# Sheet1.net
KiCad netlist of a schematic drawn in Altium Designer
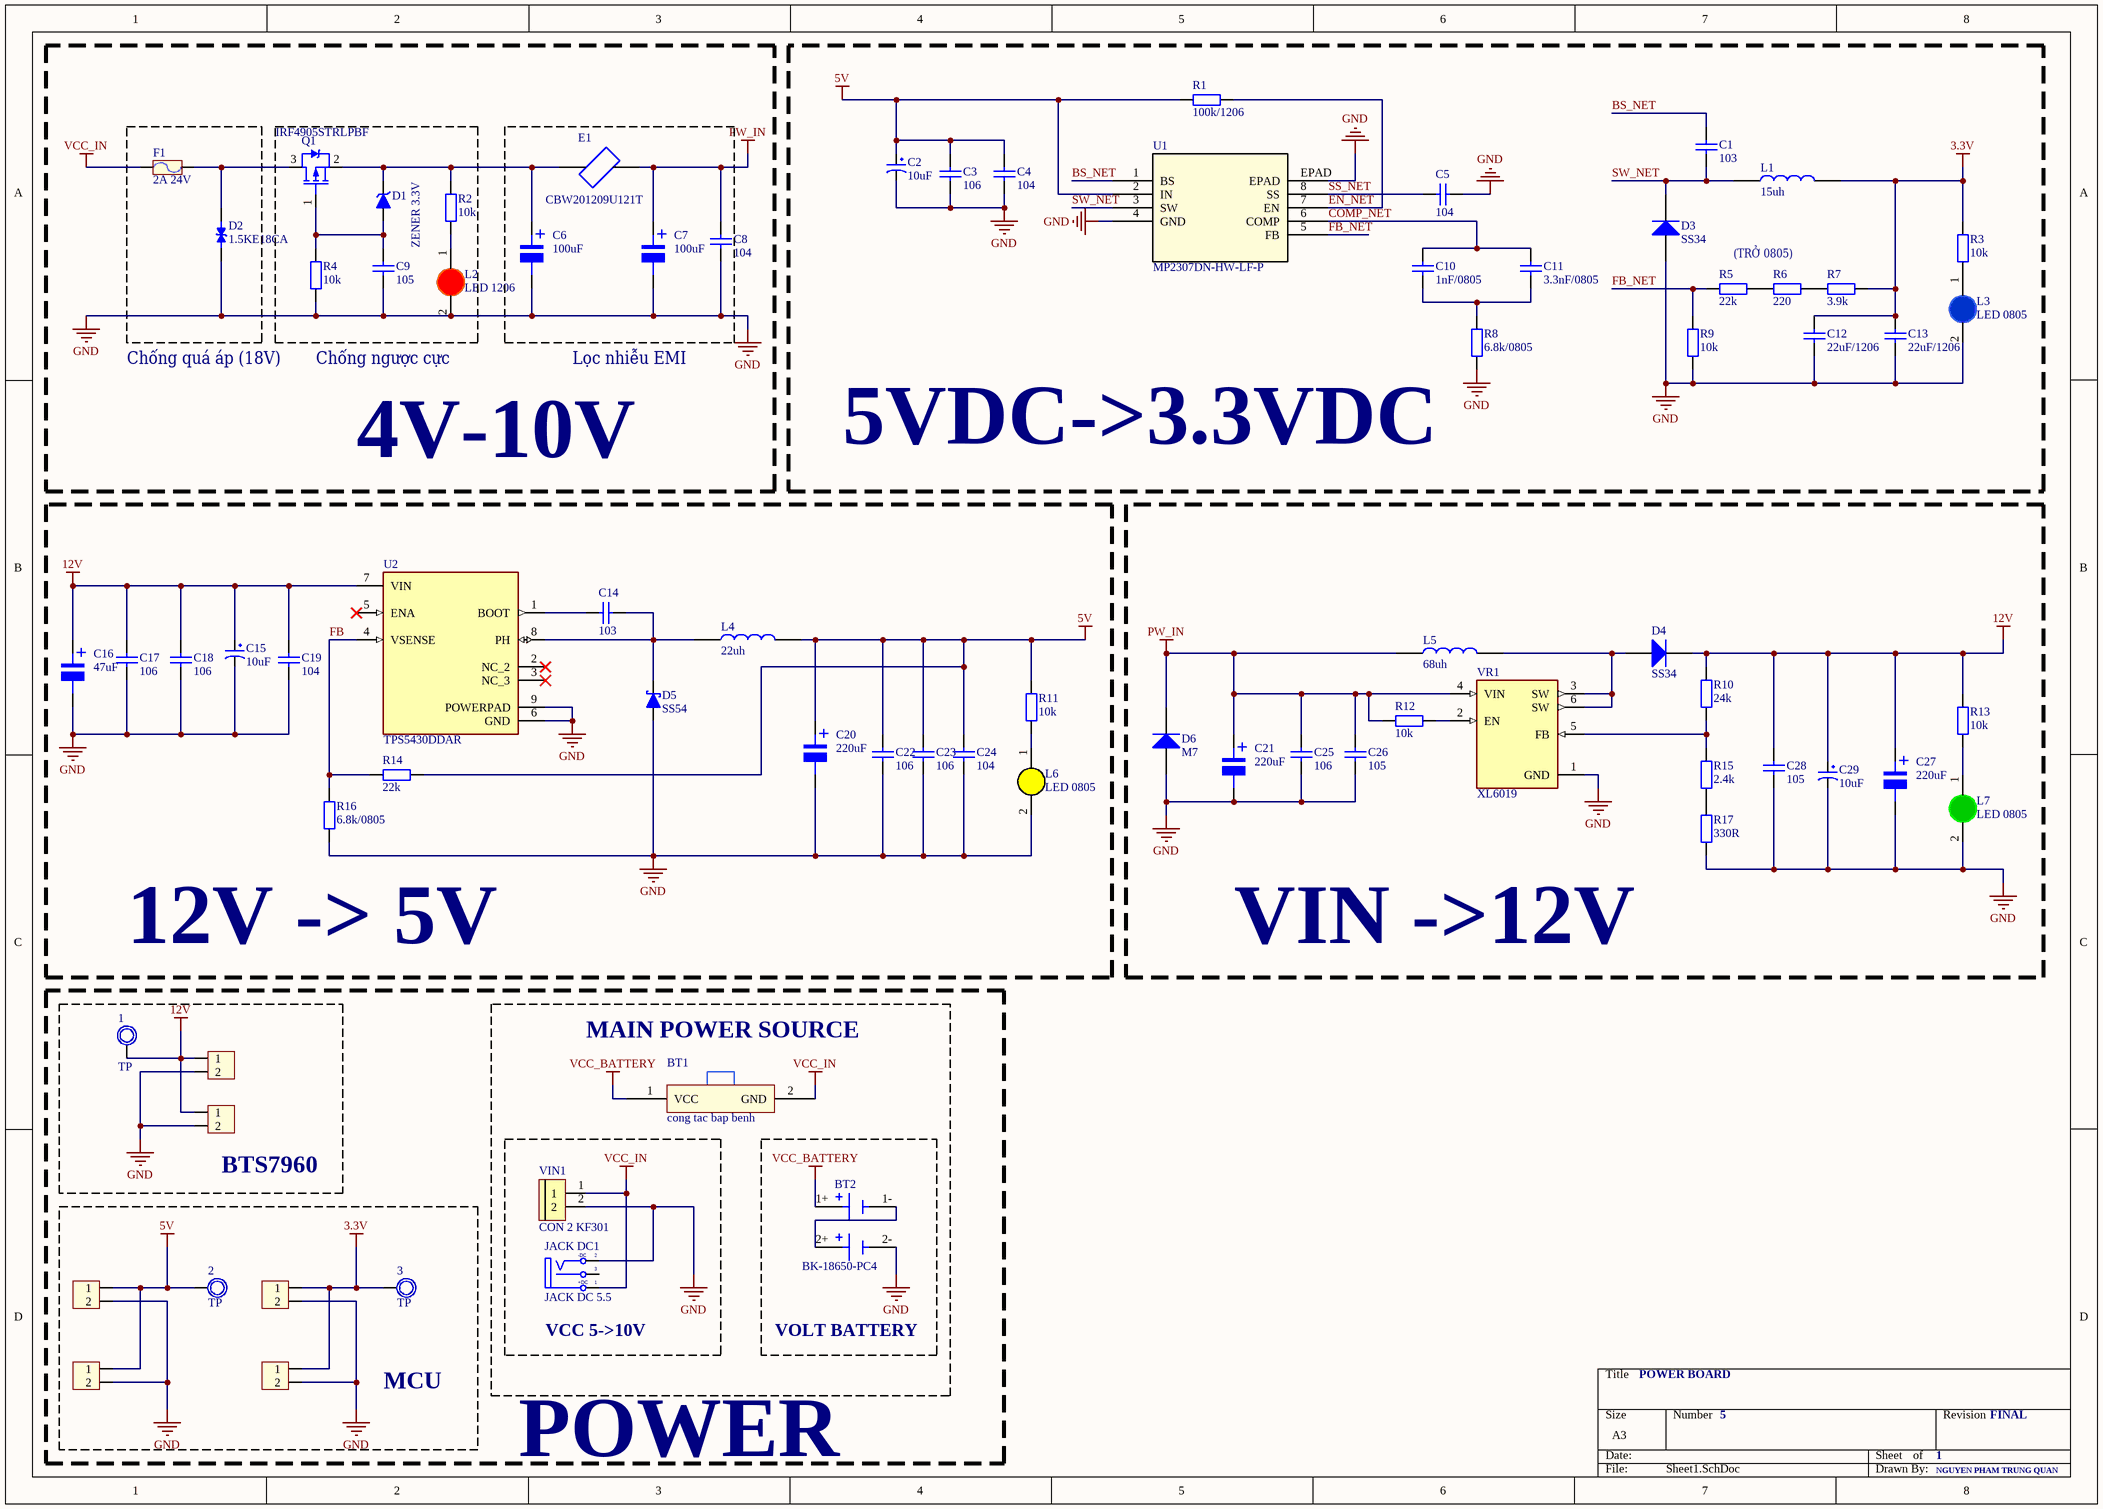
[diagram p0: Sheet1.SchDoc]

(export (version "E")
  (design (tool "Eeschema 10.0.6"))
  (components
    (comp (ref "1")
      (value "TP")
      (footprint "TP1")
      (description "Test Point")
      (libsource (lib "") (part "TP1_1"))
    )
    (comp (ref "2")
      (value "TP")
      (footprint "TP1")
      (description "Test Point")
      (libsource (lib "syhaunguyen") (part "TP1"))
    )
    (comp (ref "3")
      (value "TP")
      (footprint "TP1")
      (description "Test Point")
      (libsource (lib "syhaunguyen") (part "TP1"))
    )
    (comp (ref "BT1")
      (value "cong tac bap benh")
      (footprint "CONG TAC BAP BENH")
      (libsource (lib "Integrated_Library1") (part "cong tac bap benh"))
    )
    (comp (ref "BT2")
      (value "BK-18650-PC4")
      (footprint "BAT_BK-18650-PC4")
      (description "Battery Holder (Open) 18650 2 Cell PC Pin")
      (libsource (lib "18650_2CELL") (part "BK-18650-PC4"))
    )
    (comp (ref "C1")
      (value "103")
      (footprint "tu 1206")
      (description "Dán")
      (libsource (lib "Altium_Lib_by_KhueNguyenCreator") (part "Tu 1206 103 50V 10%"))
    )
    (comp (ref "C2")
      (value "10uF")
      (footprint "tu tantalum smd3216")
      (description "Dán")
      (libsource (lib "Altium_Lib_by_KhueNguyenCreator") (part "Tu tantalum 10uF 16V SMD3216"))
    )
    (comp (ref "C3")
      (value "106")
      (footprint "tu 0805")
      (description "Dán")
      (libsource (lib "Altium_Lib_by_KhueNguyenCreator") (part "Tu 0805 106 16V 10%"))
    )
    (comp (ref "C4")
      (value "104")
      (footprint "tu 0805")
      (description "Dán")
      (libsource (lib "Altium_Lib_by_KhueNguyenCreator") (part "Tu 0805 104 50V 10%"))
    )
    (comp (ref "C5")
      (value "104")
      (footprint "tu 0805")
      (description "Dán")
      (libsource (lib "Altium_Lib_by_KhueNguyenCreator") (part "Tu 0805 104 50V 10%"))
    )
    (comp (ref "C6")
      (value "100uF")
      (footprint "tu nhom 8 (f)")
      (description "Dán")
      (libsource (lib "Altium_Lib_by_KhueNguyenCreator") (part "Tu Nhom 100uF 50V"))
    )
    (comp (ref "C7")
      (value "100uF")
      (footprint "tu nhom 8 (f)")
      (description "Dán")
      (libsource (lib "Altium_Lib_by_KhueNguyenCreator") (part "Tu Nhom 100uF 50V"))
    )
    (comp (ref "C8")
      (value "104")
      (footprint "tu 0805")
      (description "Dán")
      (libsource (lib "Altium_Lib_by_KhueNguyenCreator") (part "Tu 0805 104 50V 10%"))
    )
    (comp (ref "C9")
      (value "105")
      (footprint "tu 0805")
      (description "Dán")
      (libsource (lib "Altium_Lib_by_KhueNguyenCreator") (part "Tu 0805 105 50V 10%"))
    )
    (comp (ref "C10")
      (value "1nF/0805")
      (footprint "tu 0805")
      (description "Dán")
      (libsource (lib "Altium_Lib_by_KhueNguyenCreator") (part "Tu 0805 102 50V 10%"))
    )
    (comp (ref "C11")
      (value "3.3nF/0805")
      (footprint "tu 0805")
      (description "Dán")
      (libsource (lib "Altium_Lib_by_KhueNguyenCreator") (part "Tu 0805 332 50V 10%"))
    )
    (comp (ref "C12")
      (value "22uF/1206")
      (footprint "tu 1206")
      (description "Dán")
      (libsource (lib "Altium_Lib_by_KhueNguyenCreator") (part "Tu 1206 226 16V 20%"))
    )
    (comp (ref "C13")
      (value "22uF/1206")
      (footprint "tu 1206")
      (description "Dán")
      (libsource (lib "Altium_Lib_by_KhueNguyenCreator") (part "Tu 1206 226 16V 20%"))
    )
    (comp (ref "C14")
      (value "103")
      (footprint "tu 1206")
      (description "Dán")
      (libsource (lib "Altium_Lib_by_KhueNguyenCreator") (part "Tu 1206 103 50V 10%"))
    )
    (comp (ref "C15")
      (value "10uF")
      (footprint "tu tantalum smd3216")
      (description "Dán")
      (libsource (lib "Altium_Lib_by_KhueNguyenCreator") (part "Tu tantalum 10uF 16V SMD3216"))
    )
    (comp (ref "C16")
      (value "47uF")
      (footprint "tu nhom 6.3 (D)")
      (description "Dán")
      (libsource (lib "Altium_Lib_by_KhueNguyenCreator") (part "Tu Nhom 47uF 16V"))
    )
    (comp (ref "C17")
      (value "106")
      (footprint "tu 0805")
      (description "Dán")
      (libsource (lib "Altium_Lib_by_KhueNguyenCreator") (part "Tu 0805 106 16V 10%"))
    )
    (comp (ref "C18")
      (value "106")
      (footprint "tu 0805")
      (description "Dán")
      (libsource (lib "Altium_Lib_by_KhueNguyenCreator") (part "Tu 0805 106 16V 10%"))
    )
    (comp (ref "C19")
      (value "104")
      (footprint "tu 0805")
      (description "Dán")
      (libsource (lib "Altium_Lib_by_KhueNguyenCreator") (part "Tu 0805 104 50V 10%"))
    )
    (comp (ref "C20")
      (value "220uF")
      (footprint "tu nhom 6.3 (d)")
      (description "Dán")
      (libsource (lib "Altium_Lib_by_KhueNguyenCreator") (part "Tu Nhom 220uF 16V"))
    )
    (comp (ref "C21")
      (value "220uF")
      (footprint "tu nhom 8 (e)")
      (description "Dán")
      (libsource (lib "Altium_Lib_by_KhueNguyenCreator") (part "Tu Nhom 220uF 10V"))
    )
    (comp (ref "C22")
      (value "106")
      (footprint "tu 0805")
      (description "Dán")
      (libsource (lib "Altium_Lib_by_KhueNguyenCreator") (part "Tu 0805 106 16V 10%"))
    )
    (comp (ref "C23")
      (value "106")
      (footprint "tu 0805")
      (description "Dán")
      (libsource (lib "Altium_Lib_by_KhueNguyenCreator") (part "Tu 0805 106 16V 10%"))
    )
    (comp (ref "C24")
      (value "104")
      (footprint "tu 0805")
      (description "Dán")
      (libsource (lib "Altium_Lib_by_KhueNguyenCreator") (part "Tu 0805 104 50V 10%"))
    )
    (comp (ref "C25")
      (value "106")
      (footprint "tu 0805")
      (description "Dán")
      (libsource (lib "Altium_Lib_by_KhueNguyenCreator") (part "Tu 0805 106 16V 10%"))
    )
    (comp (ref "C26")
      (value "105")
      (footprint "tu 0805")
      (description "Dán")
      (libsource (lib "Altium_Lib_by_KhueNguyenCreator") (part "Tu 0805 105 50V 10%"))
    )
    (comp (ref "C27")
      (value "220uF")
      (footprint "tu nhom 8 (e)")
      (description "Dán")
      (libsource (lib "Altium_Lib_by_KhueNguyenCreator") (part "Tu Nhom 220uF 10V"))
    )
    (comp (ref "C28")
      (value "105")
      (footprint "tu 0805")
      (description "Dán")
      (libsource (lib "Altium_Lib_by_KhueNguyenCreator") (part "Tu 0805 105 50V 10%"))
    )
    (comp (ref "C29")
      (value "10uF")
      (footprint "tu tantalum smd3216")
      (description "Dán")
      (libsource (lib "Altium_Lib_by_KhueNguyenCreator") (part "Tu tantalum 10uF 16V SMD3216"))
    )
    (comp (ref "D1")
      (value "ZENER 3.3V")
      (footprint "SOD123")
      (description "Zener Diode")
      (libsource (lib "chipfc_libs") (part "Diode Zener"))
    )
    (comp (ref "D2")
      (value "1.5KE18CA")
      (footprint "DIOAD1586W101L900D530")
      (description "32.5V Clamp 308A (8/20Âµs) Ipp Tvs Diode Through Hole DO-201")
      (fields (field (name "MF") "STMicroelectronics"))
      (libsource (lib "1.5KE18CA") (part "1.5KE18CA"))
    )
    (comp (ref "D3")
      (value "SS34")
      (footprint "DIODE SMA")
      (description "Dán")
      (libsource (lib "Altium_Lib_by_KhueNguyenCreator") (part "Diode SS34 ( 1N5822 )"))
    )
    (comp (ref "D4")
      (value "SS34")
      (footprint "DIODE SMA")
      (description "Dán")
      (libsource (lib "Altium_Lib_by_KhueNguyenCreator") (part "Diode SS34 ( 1N5822 )"))
    )
    (comp (ref "D5")
      (value "SS54")
      (footprint "DO-214AC (SMA)")
      (description "Schottky Diode")
      (libsource (lib "chipfc_libs") (part "Diode Schottky"))
    )
    (comp (ref "D6")
      (value "M7")
      (footprint "DIODE SMA")
      (description "Dán")
      (libsource (lib "Altium_Lib_by_KhueNguyenCreator") (part "Diode M7 ( 4007 )"))
    )
    (comp (ref "E1")
      (value "CBW201209U121T")
      (footprint "FB_LI0805H121R-10")
      (fields (field (name "MF") "Laird") (field (name "MP") "LI0805H121R-10"))
      (libsource (lib "LI0805H121R-10") (part "LI0805H121R-10"))
    )
    (comp (ref "F1")
      (value "2A 24V")
      (footprint "Cau chi tu phuc hoi 2A 24V SMD1812")
      (description "2A 24V SMD1812")
      (libsource (lib "Altium_Lib_by_KhueNguyenCreator") (part "Cau chi tu phuc hoi 2A 24V SMD1812"))
    )
    (comp (ref "H1")
      (value "Header 2P 2.54 Duc Cong")
      (footprint "Header 2P DC 2.54")
      (description "Cắm")
      (libsource (lib "") (part "Header 2P 2.54 Duc Cong_1"))
    )
    (comp (ref "H2")
      (value "Header 2P 2.54 Duc Cong")
      (footprint "Header 2P DC 2.54")
      (description "Cắm")
      (libsource (lib "") (part "Header 2P 2.54 Duc Cong_1"))
    )
    (comp (ref "H3")
      (value "Header 2P 2.54 Duc Cong")
      (footprint "Header 2P DC 2.54")
      (description "Cắm")
      (libsource (lib "Altium_Lib_by_KhueNguyenCreator") (part "Header 2P 2.54 Duc Cong"))
    )
    (comp (ref "H4")
      (value "Header 2P 2.54 Duc Cong")
      (footprint "Header 2P DC 2.54")
      (description "Cắm")
      (libsource (lib "Altium_Lib_by_KhueNguyenCreator") (part "Header 2P 2.54 Duc Cong"))
    )
    (comp (ref "H5")
      (value "Header 2P 2.54 Duc Cong")
      (footprint "Header 2P DC 2.54")
      (description "Cắm")
      (libsource (lib "Altium_Lib_by_KhueNguyenCreator") (part "Header 2P 2.54 Duc Cong"))
    )
    (comp (ref "H6")
      (value "Header 2P 2.54 Duc Cong")
      (footprint "Header 2P DC 2.54")
      (description "Cắm")
      (libsource (lib "Altium_Lib_by_KhueNguyenCreator") (part "Header 2P 2.54 Duc Cong"))
    )
    (comp (ref "JACK DC1")
      (value "JACK DC 5.5")
      (footprint "JACK DC 5.5")
      (libsource (lib "Altium_Lib_by_KhueNguyenCreator") (part "JACK DC 5.5"))
    )
    (comp (ref "L1")
      (value "15uh")
      (footprint "Cuon Cam 12x12x10")
      (description "Dán")
      (libsource (lib "Altium_Lib_by_KhueNguyenCreator") (part "CUON CAM 100uH SMD"))
    )
    (comp (ref "L2")
      (value "LED 1206")
      (footprint "LED-1206-Red")
      (description "Dán")
      (libsource (lib "Altium_Lib_by_KhueNguyenCreator") (part "LED 1206 Do"))
    )
    (comp (ref "L3")
      (value "LED 0805")
      (footprint "LED-1206-Blue")
      (description "Dán")
      (libsource (lib "Altium_Lib_by_KhueNguyenCreator") (part "LED 1206 Xanh Duong"))
    )
    (comp (ref "L4")
      (value "22uh")
      (footprint "Cuon Cam 12x12x10")
      (description "Dán")
      (libsource (lib "Altium_Lib_by_KhueNguyenCreator") (part "CUON CAM 100uH SMD"))
    )
    (comp (ref "L5")
      (value "68uh")
      (footprint "Cuon Cam 12x12x10")
      (description "Dán")
      (libsource (lib "Altium_Lib_by_KhueNguyenCreator") (part "CUON CAM 100uH SMD"))
    )
    (comp (ref "L6")
      (value "LED 0805")
      (footprint "LED-1206-Yellow")
      (description "Dán")
      (libsource (lib "Altium_Lib_by_KhueNguyenCreator") (part "LED 1206 Vang"))
    )
    (comp (ref "L7")
      (value "LED 0805")
      (footprint "LED-1206-Green")
      (description "Dán")
      (libsource (lib "Altium_Lib_by_KhueNguyenCreator") (part "LED 1206 Xanh La"))
    )
    (comp (ref "Q1")
      (value "IRF4905STRLPBF")
      (footprint "TO-263 (D2PAK)")
      (description "Mosfet P")
      (libsource (lib "chipfc_libs") (part "Mosfet P"))
    )
    (comp (ref "R1")
      (value "100k/1206")
      (footprint "tro smd 1206")
      (description "Dán")
      (libsource (lib "Altium_Lib_by_KhueNguyenCreator") (part "Tro 1206 1% 100K"))
    )
    (comp (ref "R2")
      (value "10k")
      (footprint "tro smd 0805")
      (description "Dán")
      (libsource (lib "Altium_Lib_by_KhueNguyenCreator") (part "Tro 0805 5% 10k"))
    )
    (comp (ref "R3")
      (value "10k")
      (footprint "tro smd 0805")
      (description "Dán")
      (libsource (lib "Altium_Lib_by_KhueNguyenCreator") (part "Tro 0805 5% 10k"))
    )
    (comp (ref "R4")
      (value "10k")
      (footprint "tro smd 0805")
      (description "Dán")
      (libsource (lib "Altium_Lib_by_KhueNguyenCreator") (part "Tro 0805 5% 10k"))
    )
    (comp (ref "R5")
      (value "22k")
      (footprint "tro smd 0805")
      (description "Dán")
      (libsource (lib "Altium_Lib_by_KhueNguyenCreator") (part "Tro 0805 5% 22k"))
    )
    (comp (ref "R6")
      (value "220")
      (footprint "tro smd 0805")
      (description "Dán")
      (libsource (lib "Altium_Lib_by_KhueNguyenCreator") (part "Tro 0805 5% 220R"))
    )
    (comp (ref "R7")
      (value "3.9k")
      (footprint "Tro SMD 0805")
      (description "Dán")
      (libsource (lib "Altium_Lib_by_KhueNguyenCreator") (part "Tro 0805 5% 3.9k"))
    )
    (comp (ref "R8")
      (value "6.8k/0805")
      (footprint "tro smd 0805")
      (description "Dán")
      (libsource (lib "Altium_Lib_by_KhueNguyenCreator") (part "Tro 0805 5% 6.8k"))
    )
    (comp (ref "R9")
      (value "10k")
      (footprint "tro smd 0805")
      (description "Dán")
      (libsource (lib "Altium_Lib_by_KhueNguyenCreator") (part "Tro 0805 5% 10k"))
    )
    (comp (ref "R10")
      (value "24k")
      (footprint "tro smd 0805")
      (description "Dán")
      (libsource (lib "Altium_Lib_by_KhueNguyenCreator") (part "Tro 0805 5% 22k"))
    )
    (comp (ref "R11")
      (value "10k")
      (footprint "tro smd 0805")
      (description "Dán")
      (libsource (lib "Altium_Lib_by_KhueNguyenCreator") (part "Tro 0805 5% 10k"))
    )
    (comp (ref "R12")
      (value "10k")
      (footprint "tro smd 0805")
      (description "Dán")
      (libsource (lib "Altium_Lib_by_KhueNguyenCreator") (part "Tro 0805 5% 10k"))
    )
    (comp (ref "R13")
      (value "10k")
      (footprint "tro smd 0805")
      (description "Dán")
      (libsource (lib "Altium_Lib_by_KhueNguyenCreator") (part "Tro 0805 5% 10k"))
    )
    (comp (ref "R14")
      (value "22k")
      (footprint "tro smd 0805")
      (description "Dán")
      (libsource (lib "Altium_Lib_by_KhueNguyenCreator") (part "Tro 0805 5% 22k"))
    )
    (comp (ref "R15")
      (value "2.4k")
      (footprint "Tro SMD 0805")
      (description "Dán")
      (libsource (lib "Altium_Lib_by_KhueNguyenCreator") (part "Tro 0805 5% 2k"))
    )
    (comp (ref "R16")
      (value "6.8k/0805")
      (footprint "tro smd 0805")
      (description "Dán")
      (libsource (lib "Altium_Lib_by_KhueNguyenCreator") (part "Tro 0805 5% 6.8k"))
    )
    (comp (ref "R17")
      (value "330R")
      (footprint "Tro SMD 0805")
      (description "Dán")
      (libsource (lib "Altium_Lib_by_KhueNguyenCreator") (part "Tro 0805 5% 330R"))
    )
    (comp (ref "U1")
      (value "MP2307DN-HW-LF-P")
      (footprint "IC8_MP2307_MNP")
      (description "3A 23V 340KHz Synchronous Rectified Step-Down Converter")
      (fields (field (name "COPYRIGHT") "Copyright (C) 2025 Ultra Librarian. All rights reserved."))
      (libsource (lib "MP2307DN-HW-LF-P") (part "MP2307DN-HW-LF-P"))
    )
    (comp (ref "U2")
      (value "TPS5430DDAR")
      (footprint "CONV_TPS5430DDAR")
      (description "5.5V to 36V Input, 3A, 500kHz Step-Down Converter")
      (fields (field (name "MF") "Texas Instruments"))
      (libsource (lib "TPS5430DDAR") (part "TPS5430DDAR"))
    )
    (comp (ref "VIN1")
      (value "CON 2 KF301")
      (footprint "Con 2 KF301 5.08")
      (description "Cắm")
      (libsource (lib "Altium_Lib_by_KhueNguyenCreator") (part "CON 2 KF301"))
    )
    (comp (ref "VR1")
      (value "XL6019")
      (footprint "DPAK170P1435X465-6N")
      (fields (field (name "MF") "XLSEMI") (field (name "MP") "XL6009"))
      (libsource (lib "XL6009") (part "XL6009"))
    )
  )
  (nets
    (net (code "1") (name "/BS_NET") (class "Default")
      (node (ref "C1") (pin "1") (pinfunction "1_1") (pintype "passive"))
      (node (ref "U1") (pin "1") (pinfunction "BS_1") (pintype "passive"))
    )
    (net (code "2") (name "/COMP_NET") (class "Default")
      (node (ref "C10") (pin "1") (pinfunction "1_1") (pintype "passive"))
      (node (ref "C11") (pin "1") (pinfunction "1_1") (pintype "passive"))
      (node (ref "U1") (pin "6") (pinfunction "COMP_6") (pintype "passive"))
    )
    (net (code "3") (name "/EN_NET") (class "Default")
      (node (ref "R1") (pin "1") (pinfunction "1_1") (pintype "passive"))
      (node (ref "U1") (pin "7") (pinfunction "EN_7") (pintype "passive"))
    )
    (net (code "4") (name "/FB") (class "Default")
      (node (ref "R14") (pin "1") (pinfunction "1_1") (pintype "passive"))
      (node (ref "R16") (pin "1") (pinfunction "1_1") (pintype "passive"))
      (node (ref "U2") (pin "4") (pinfunction "VSENSE_4") (pintype "input"))
    )
    (net (code "5") (name "/FB_NET") (class "Default")
      (node (ref "R5") (pin "1") (pinfunction "1_1") (pintype "passive"))
      (node (ref "R9") (pin "2") (pinfunction "2_2") (pintype "passive"))
      (node (ref "U1") (pin "5") (pinfunction "FB_5") (pintype "passive"))
    )
    (net (code "6") (name "/SS_NET") (class "Default")
      (node (ref "C5") (pin "1") (pinfunction "1_1") (pintype "passive"))
      (node (ref "U1") (pin "8") (pinfunction "SS_8") (pintype "passive"))
    )
    (net (code "7") (name "/SW_NET") (class "Default")
      (node (ref "C1") (pin "2") (pinfunction "2_2") (pintype "passive"))
      (node (ref "D3") (pin "2") (pinfunction "K_2") (pintype "passive"))
      (node (ref "L1") (pin "1") (pinfunction "1_1") (pintype "passive"))
      (node (ref "U1") (pin "3") (pinfunction "SW_3") (pintype "passive"))
    )
    (net (code "8") (name "3.3V") (class "Default")
      (node (ref "3") (pin "1") (pinfunction "1_1") (pintype "passive"))
      (node (ref "C12") (pin "1") (pinfunction "1_1") (pintype "passive"))
      (node (ref "C13") (pin "1") (pinfunction "1_1") (pintype "passive"))
      (node (ref "H4") (pin "1") (pinfunction "1_1") (pintype "passive"))
      (node (ref "H6") (pin "1") (pinfunction "1_1") (pintype "passive"))
      (node (ref "L1") (pin "2") (pinfunction "2_2") (pintype "passive"))
      (node (ref "R3") (pin "2") (pinfunction "2_2") (pintype "passive"))
      (node (ref "R7") (pin "2") (pinfunction "2_2") (pintype "passive"))
    )
    (net (code "9") (name "5V") (class "Default")
      (node (ref "2") (pin "1") (pinfunction "1_1") (pintype "passive"))
      (node (ref "C2") (pin "1") (pinfunction "1_1") (pintype "passive"))
      (node (ref "C20") (pin "1") (pinfunction "1_1") (pintype "passive"))
      (node (ref "C22") (pin "1") (pinfunction "1_1") (pintype "passive"))
      (node (ref "C23") (pin "1") (pinfunction "1_1") (pintype "passive"))
      (node (ref "C24") (pin "1") (pinfunction "1_1") (pintype "passive"))
      (node (ref "C3") (pin "1") (pinfunction "1_1") (pintype "passive"))
      (node (ref "C4") (pin "1") (pinfunction "1_1") (pintype "passive"))
      (node (ref "H3") (pin "1") (pinfunction "1_1") (pintype "passive"))
      (node (ref "H5") (pin "1") (pinfunction "1_1") (pintype "passive"))
      (node (ref "L4") (pin "2") (pinfunction "2_2") (pintype "passive"))
      (node (ref "R1") (pin "2") (pinfunction "2_2") (pintype "passive"))
      (node (ref "R11") (pin "1") (pinfunction "1_1") (pintype "passive"))
      (node (ref "R14") (pin "2") (pinfunction "2_2") (pintype "passive"))
      (node (ref "U1") (pin "2") (pinfunction "IN_2") (pintype "passive"))
    )
    (net (code "10") (name "12V") (class "Default")
      (node (ref "1") (pin "1") (pinfunction "1_1") (pintype "passive"))
      (node (ref "C15") (pin "1") (pinfunction "1_1") (pintype "passive"))
      (node (ref "C16") (pin "1") (pinfunction "1_1") (pintype "passive"))
      (node (ref "C17") (pin "1") (pinfunction "1_1") (pintype "passive"))
      (node (ref "C18") (pin "1") (pinfunction "1_1") (pintype "passive"))
      (node (ref "C19") (pin "1") (pinfunction "1_1") (pintype "passive"))
      (node (ref "C27") (pin "1") (pinfunction "1_1") (pintype "passive"))
      (node (ref "C28") (pin "1") (pinfunction "1_1") (pintype "passive"))
      (node (ref "C29") (pin "1") (pinfunction "1_1") (pintype "passive"))
      (node (ref "D4") (pin "2") (pinfunction "K_2") (pintype "passive"))
      (node (ref "H1") (pin "1") (pinfunction "1_1") (pintype "passive"))
      (node (ref "H2") (pin "1") (pinfunction "1_1") (pintype "passive"))
      (node (ref "R10") (pin "2") (pinfunction "2_2") (pintype "passive"))
      (node (ref "R13") (pin "1") (pinfunction "1_1") (pintype "passive"))
      (node (ref "U2") (pin "7") (pinfunction "VIN_7") (pintype "power_in"))
    )
    (net (code "11") (name "GND") (class "Default")
      (node (ref "BT2") (pin "2-") (pinfunction "2-_2-") (pintype "passive"))
      (node (ref "C12") (pin "2") (pinfunction "2_2") (pintype "passive"))
      (node (ref "C13") (pin "2") (pinfunction "2_2") (pintype "passive"))
      (node (ref "C15") (pin "2") (pinfunction "2_2") (pintype "passive"))
      (node (ref "C16") (pin "2") (pinfunction "2_2") (pintype "passive"))
      (node (ref "C17") (pin "2") (pinfunction "2_2") (pintype "passive"))
      (node (ref "C18") (pin "2") (pinfunction "2_2") (pintype "passive"))
      (node (ref "C19") (pin "2") (pinfunction "2_2") (pintype "passive"))
      (node (ref "C2") (pin "2") (pinfunction "2_2") (pintype "passive"))
      (node (ref "C20") (pin "2") (pinfunction "2_2") (pintype "passive"))
      (node (ref "C21") (pin "2") (pinfunction "2_2") (pintype "passive"))
      (node (ref "C22") (pin "2") (pinfunction "2_2") (pintype "passive"))
      (node (ref "C23") (pin "2") (pinfunction "2_2") (pintype "passive"))
      (node (ref "C24") (pin "2") (pinfunction "2_2") (pintype "passive"))
      (node (ref "C25") (pin "2") (pinfunction "2_2") (pintype "passive"))
      (node (ref "C26") (pin "2") (pinfunction "2_2") (pintype "passive"))
      (node (ref "C27") (pin "2") (pinfunction "2_2") (pintype "passive"))
      (node (ref "C28") (pin "2") (pinfunction "2_2") (pintype "passive"))
      (node (ref "C29") (pin "2") (pinfunction "2_2") (pintype "passive"))
      (node (ref "C3") (pin "2") (pinfunction "2_2") (pintype "passive"))
      (node (ref "C4") (pin "2") (pinfunction "2_2") (pintype "passive"))
      (node (ref "C5") (pin "2") (pinfunction "2_2") (pintype "passive"))
      (node (ref "C6") (pin "2") (pinfunction "2_2") (pintype "passive"))
      (node (ref "C7") (pin "2") (pinfunction "2_2") (pintype "passive"))
      (node (ref "C8") (pin "2") (pinfunction "2_2") (pintype "passive"))
      (node (ref "C9") (pin "2") (pinfunction "2_2") (pintype "passive"))
      (node (ref "D2") (pin "1") (pinfunction "1_1") (pintype "passive"))
      (node (ref "D3") (pin "1") (pinfunction "A_1") (pintype "passive"))
      (node (ref "D5") (pin "1") (pinfunction "A_1") (pintype "passive"))
      (node (ref "D6") (pin "1") (pinfunction "A_1") (pintype "passive"))
      (node (ref "H1") (pin "2") (pinfunction "2_2") (pintype "passive"))
      (node (ref "H2") (pin "2") (pinfunction "2_2") (pintype "passive"))
      (node (ref "H3") (pin "2") (pinfunction "2_2") (pintype "passive"))
      (node (ref "H4") (pin "2") (pinfunction "2_2") (pintype "passive"))
      (node (ref "H5") (pin "2") (pinfunction "2_2") (pintype "passive"))
      (node (ref "H6") (pin "2") (pinfunction "2_2") (pintype "passive"))
      (node (ref "JACK DC1") (pin "2") (pinfunction "TN_2") (pintype "passive"))
      (node (ref "L2") (pin "2") (pinfunction "K_2") (pintype "passive"))
      (node (ref "L3") (pin "2") (pinfunction "K_2") (pintype "passive"))
      (node (ref "L6") (pin "2") (pinfunction "K_2") (pintype "passive"))
      (node (ref "L7") (pin "2") (pinfunction "K_2") (pintype "passive"))
      (node (ref "R16") (pin "2") (pinfunction "2_2") (pintype "passive"))
      (node (ref "R17") (pin "2") (pinfunction "2_2") (pintype "passive"))
      (node (ref "R4") (pin "1") (pinfunction "1_1") (pintype "passive"))
      (node (ref "R8") (pin "2") (pinfunction "2_2") (pintype "passive"))
      (node (ref "R9") (pin "1") (pinfunction "1_1") (pintype "passive"))
      (node (ref "U1") (pin "4") (pinfunction "GND_4") (pintype "power_in"))
      (node (ref "U1") (pin "EPAD") (pinfunction "EPAD_EPAD") (pintype "passive"))
      (node (ref "U2") (pin "6") (pinfunction "GND_6") (pintype "power_in"))
      (node (ref "U2") (pin "9") (pinfunction "POWERPAD_9") (pintype "power_in"))
      (node (ref "VIN1") (pin "2") (pinfunction "2_2") (pintype "passive"))
      (node (ref "VR1") (pin "1") (pinfunction "GND_1") (pintype "power_in"))
    )
    (net (code "12") (name "Net-(BT2-Pad1-)") (class "Default")
      (node (ref "BT2") (pin "1-") (pinfunction "1-_1-") (pintype "passive"))
      (node (ref "BT2") (pin "2+") (pinfunction "2+_2+") (pintype "passive"))
    )
    (net (code "13") (name "Net-(C10-Pad2)") (class "Default")
      (node (ref "C10") (pin "2") (pinfunction "2_2") (pintype "passive"))
      (node (ref "C11") (pin "2") (pinfunction "2_2") (pintype "passive"))
      (node (ref "R8") (pin "1") (pinfunction "1_1") (pintype "passive"))
    )
    (net (code "14") (name "Net-(D1-A)") (class "Default")
      (node (ref "C9") (pin "1") (pinfunction "1_1") (pintype "passive"))
      (node (ref "D1") (pin "1") (pinfunction "A_1") (pintype "passive"))
      (node (ref "Q1") (pin "1") (pinfunction "G_1") (pintype "passive"))
      (node (ref "R4") (pin "2") (pinfunction "2_2") (pintype "passive"))
    )
    (net (code "15") (name "Net-(D1-K)") (class "Default")
      (node (ref "C6") (pin "1") (pinfunction "1_1") (pintype "passive"))
      (node (ref "D1") (pin "2") (pinfunction "K_2") (pintype "passive"))
      (node (ref "E1") (pin "1") (pinfunction "1_1") (pintype "passive"))
      (node (ref "Q1") (pin "2") (pinfunction "S_2") (pintype "passive"))
      (node (ref "R2") (pin "2") (pinfunction "2_2") (pintype "passive"))
    )
    (net (code "16") (name "Net-(D4-A)") (class "Default")
      (node (ref "D4") (pin "1") (pinfunction "A_1") (pintype "passive"))
      (node (ref "L5") (pin "2") (pinfunction "2_2") (pintype "passive"))
      (node (ref "VR1") (pin "3") (pinfunction "SW_3") (pintype "output"))
      (node (ref "VR1") (pin "6") (pinfunction "SW_6") (pintype "output"))
    )
    (net (code "17") (name "Net-(D5-K)") (class "Default")
      (node (ref "C14") (pin "2") (pinfunction "2_2") (pintype "passive"))
      (node (ref "D5") (pin "2") (pinfunction "K_2") (pintype "passive"))
      (node (ref "L4") (pin "1") (pinfunction "1_1") (pintype "passive"))
      (node (ref "U2") (pin "8") (pinfunction "PH_8") (pintype "bidirectional"))
    )
    (net (code "18") (name "Net-(L2-A)") (class "Default")
      (node (ref "L2") (pin "1") (pinfunction "A_1") (pintype "passive"))
      (node (ref "R2") (pin "1") (pinfunction "1_1") (pintype "passive"))
    )
    (net (code "19") (name "Net-(L3-A)") (class "Default")
      (node (ref "L3") (pin "1") (pinfunction "A_1") (pintype "passive"))
      (node (ref "R3") (pin "1") (pinfunction "1_1") (pintype "passive"))
    )
    (net (code "20") (name "Net-(L6-A)") (class "Default")
      (node (ref "L6") (pin "1") (pinfunction "A_1") (pintype "passive"))
      (node (ref "R11") (pin "2") (pinfunction "2_2") (pintype "passive"))
    )
    (net (code "21") (name "Net-(L7-A)") (class "Default")
      (node (ref "L7") (pin "1") (pinfunction "A_1") (pintype "passive"))
      (node (ref "R13") (pin "2") (pinfunction "2_2") (pintype "passive"))
    )
    (net (code "22") (name "Net-(Q1-D)") (class "Default")
      (node (ref "D2") (pin "2") (pinfunction "2_2") (pintype "passive"))
      (node (ref "F1") (pin "2") (pinfunction "2_2") (pintype "passive"))
      (node (ref "Q1") (pin "3") (pinfunction "D_3") (pintype "passive"))
    )
    (net (code "23") (name "Net-(R5-Pad2)") (class "Default")
      (node (ref "R5") (pin "2") (pinfunction "2_2") (pintype "passive"))
      (node (ref "R6") (pin "1") (pinfunction "1_1") (pintype "passive"))
    )
    (net (code "24") (name "Net-(R6-Pad2)") (class "Default")
      (node (ref "R6") (pin "2") (pinfunction "2_2") (pintype "passive"))
      (node (ref "R7") (pin "1") (pinfunction "1_1") (pintype "passive"))
    )
    (net (code "25") (name "Net-(R15-Pad1)") (class "Default")
      (node (ref "R15") (pin "1") (pinfunction "1_1") (pintype "passive"))
      (node (ref "R17") (pin "1") (pinfunction "1_1") (pintype "passive"))
    )
    (net (code "26") (name "Net-(U2-BOOT)") (class "Default")
      (node (ref "C14") (pin "1") (pinfunction "1_1") (pintype "passive"))
      (node (ref "U2") (pin "1") (pinfunction "BOOT_1") (pintype "output"))
    )
    (net (code "27") (name "Net-(VR1-EN)") (class "Default")
      (node (ref "R12") (pin "1") (pinfunction "1_1") (pintype "passive"))
      (node (ref "VR1") (pin "2") (pinfunction "EN_2") (pintype "input"))
    )
    (net (code "28") (name "Net-(VR1-FB)") (class "Default")
      (node (ref "R10") (pin "1") (pinfunction "1_1") (pintype "passive"))
      (node (ref "R15") (pin "2") (pinfunction "2_2") (pintype "passive"))
      (node (ref "VR1") (pin "5") (pinfunction "FB_5") (pintype "input"))
    )
    (net (code "29") (name "PW_IN") (class "Default")
      (node (ref "C21") (pin "1") (pinfunction "1_1") (pintype "passive"))
      (node (ref "C25") (pin "1") (pinfunction "1_1") (pintype "passive"))
      (node (ref "C26") (pin "1") (pinfunction "1_1") (pintype "passive"))
      (node (ref "C7") (pin "1") (pinfunction "1_1") (pintype "passive"))
      (node (ref "C8") (pin "1") (pinfunction "1_1") (pintype "passive"))
      (node (ref "D6") (pin "2") (pinfunction "K_2") (pintype "passive"))
      (node (ref "E1") (pin "2") (pinfunction "2_2") (pintype "passive"))
      (node (ref "L5") (pin "1") (pinfunction "1_1") (pintype "passive"))
      (node (ref "R12") (pin "2") (pinfunction "2_2") (pintype "passive"))
      (node (ref "VR1") (pin "4") (pinfunction "VIN_4") (pintype "input"))
    )
    (net (code "30") (name "VCC_BATTERY") (class "Default")
      (node (ref "BT1") (pin "1") (pinfunction "VCC_1") (pintype "passive"))
      (node (ref "BT2") (pin "1+") (pinfunction "1+_1+") (pintype "passive"))
    )
    (net (code "31") (name "VCC_IN") (class "Default")
      (node (ref "BT1") (pin "2") (pinfunction "GND_2") (pintype "passive"))
      (node (ref "F1") (pin "1") (pinfunction "1_1") (pintype "passive"))
      (node (ref "JACK DC1") (pin "1") (pinfunction "T_1") (pintype "passive"))
      (node (ref "VIN1") (pin "1") (pinfunction "1_1") (pintype "passive"))
    )
    (net (code "32") (name "unconnected-(JACK DC1-S-Pad3)") (class "Default")
      (node (ref "JACK DC1") (pin "3") (pinfunction "S_3") (pintype "power_in"))
    )
    (net (code "33") (name "unconnected-(U2-ENA-Pad5)") (class "Default")
      (node (ref "U2") (pin "5") (pinfunction "ENA_5") (pintype "input+no_connect"))
    )
    (net (code "34") (name "unconnected-(U2-NC_2-Pad2)") (class "Default")
      (node (ref "U2") (pin "2") (pinfunction "NC_2_2") (pintype "passive+no_connect"))
    )
    (net (code "35") (name "unconnected-(U2-NC_3-Pad3)") (class "Default")
      (node (ref "U2") (pin "3") (pinfunction "NC_3_3") (pintype "passive+no_connect"))
    )
  )
)
